# Mixer-v1.net
KiCad netlist of a schematic drawn in EAGLE
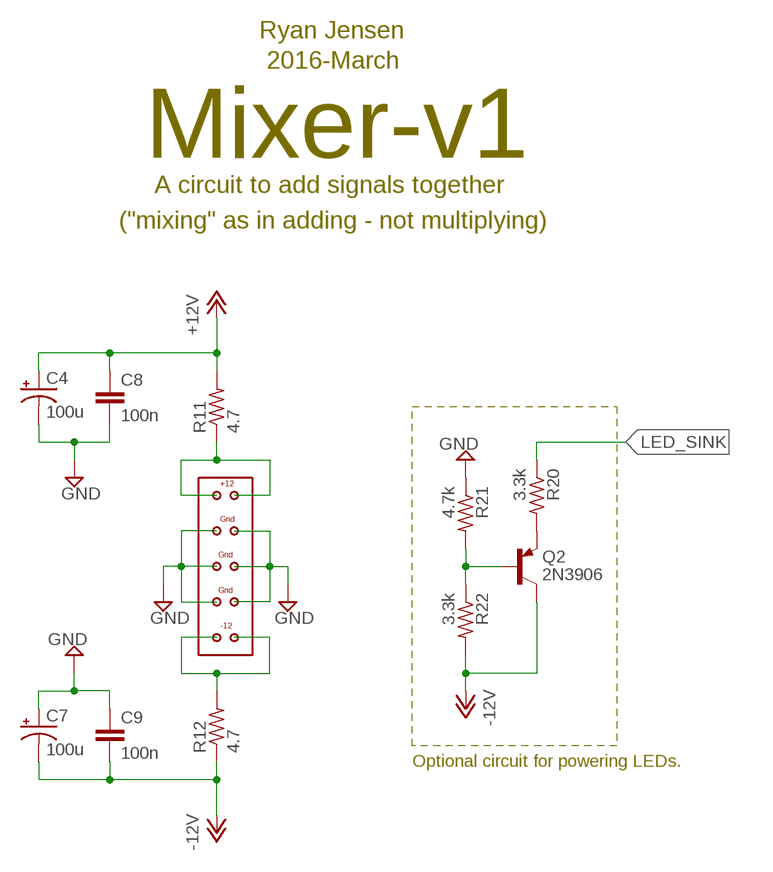
[diagram p0: schematic, sheet 1]
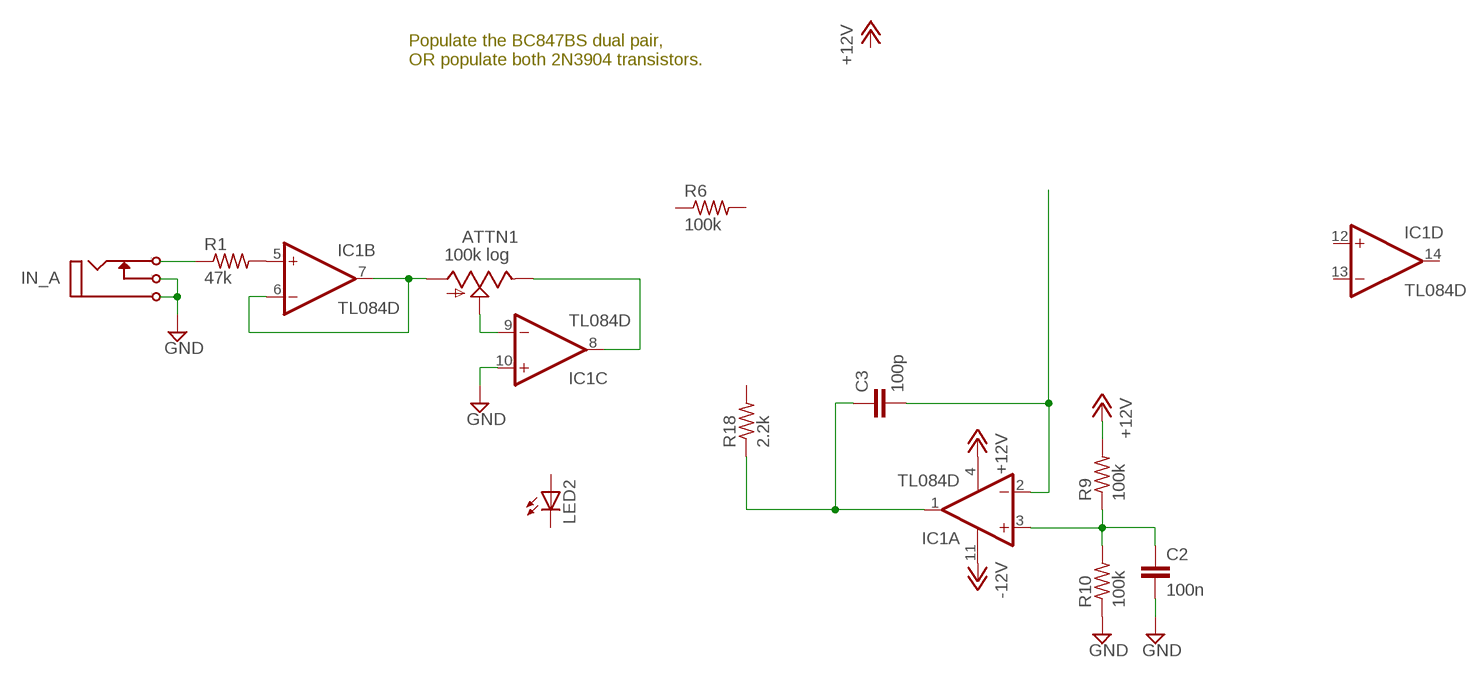
[diagram p1: schematic, sheet 2]

(export (version "E")
  (design (tool "Eeschema 10.0.6"))
  (components
    (comp (ref "ATTN1")
      (value "100k log")
      (footprint "eagle-import:B64Y")
      (libsource (lib "eagle-import") (part "TRIM_US-B64Y"))
    )
    (comp (ref "C2")
      (value "100n")
      (footprint "eagle-import:C0603")
      (libsource (lib "eagle-import") (part "C-EUC0603"))
    )
    (comp (ref "C3")
      (value "100p")
      (footprint "eagle-import:C0603")
      (libsource (lib "eagle-import") (part "C-EUC0603"))
    )
    (comp (ref "IC1")
      (value "TL084D")
      (footprint "eagle-import:SO14")
      (libsource (lib "eagle-import") (part "TL084D"))
    )
    (comp (ref "IN_A")
      (value "CV")
      (footprint "eagle-import:MONO_JACK")
      (libsource (lib "eagle-import") (part "MONO_JACK"))
    )
    (comp (ref "LED2")
      (value "LED_ELD260")
      (footprint "eagle-import:LED_LD260")
      (libsource (lib "eagle-import") (part "LED_ELD260"))
    )
    (comp (ref "R1")
      (value "47k")
      (footprint "eagle-import:R0603")
      (libsource (lib "eagle-import") (part "R-US_R0603"))
    )
    (comp (ref "R6")
      (value "100k")
      (footprint "eagle-import:R0603")
      (libsource (lib "eagle-import") (part "R-US_R0603"))
    )
    (comp (ref "R9")
      (value "100k")
      (footprint "eagle-import:R0603")
      (libsource (lib "eagle-import") (part "R-US_R0603"))
    )
    (comp (ref "R10")
      (value "100k")
      (footprint "eagle-import:R0603")
      (libsource (lib "eagle-import") (part "R-US_R0603"))
    )
    (comp (ref "R18")
      (value "2.2k")
      (footprint "eagle-import:R0603")
      (libsource (lib "eagle-import") (part "R-US_R0603"))
    )
    (comp (ref "C4")
      (value "100u")
      (footprint "eagle-import:E2,5-7")
      (libsource (lib "eagle-import") (part "CPOL-USE2.5-7"))
    )
    (comp (ref "C7")
      (value "100u")
      (footprint "eagle-import:E2,5-7")
      (libsource (lib "eagle-import") (part "CPOL-USE2.5-7"))
    )
    (comp (ref "C8")
      (value "100n")
      (footprint "eagle-import:C0603")
      (libsource (lib "eagle-import") (part "C-EUC0603"))
    )
    (comp (ref "C9")
      (value "100n")
      (footprint "eagle-import:C0603")
      (libsource (lib "eagle-import") (part "C-EUC0603"))
    )
    (comp (ref "Q2")
      (value "2N3906")
      (footprint "eagle-import:TO92")
      (libsource (lib "eagle-import") (part "2N3906"))
    )
    (comp (ref "R11")
      (value "4.7")
      (footprint "eagle-import:R0603")
      (libsource (lib "eagle-import") (part "R-US_R0603"))
    )
    (comp (ref "R12")
      (value "4.7")
      (footprint "eagle-import:R0603")
      (libsource (lib "eagle-import") (part "R-US_R0603"))
    )
    (comp (ref "R20")
      (value "3.3k")
      (footprint "eagle-import:R0603")
      (libsource (lib "eagle-import") (part "R-US_R0603"))
    )
    (comp (ref "R21")
      (value "4.7k")
      (footprint "eagle-import:R0603")
      (libsource (lib "eagle-import") (part "R-US_R0603"))
    )
    (comp (ref "R22")
      (value "3.3k")
      (footprint "eagle-import:R0603")
      (libsource (lib "eagle-import") (part "R-US_R0603"))
    )
    (comp (ref "U$3")
      (value "EURORACK-POWER")
      (footprint "eagle-import:EURORACK-POWER")
      (libsource (lib "eagle-import") (part "EURORACK-POWER"))
    )
  )
  (nets
    (net (code "1") (name "+12V") (class "Default")
      (node (ref "C4") (pin "+") (pinfunction "+_+") (pintype "passive"))
      (node (ref "C8") (pin "1") (pinfunction "1_1") (pintype "passive"))
      (node (ref "IC1") (pin "4") (pinfunction "V+_4") (pintype "power_in"))
      (node (ref "R11") (pin "2") (pinfunction "2_2") (pintype "passive"))
      (node (ref "R9") (pin "2") (pinfunction "2_2") (pintype "passive"))
    )
    (net (code "2") (name "-12V") (class "Default")
      (node (ref "C7") (pin "-") (pinfunction "-_-") (pintype "passive"))
      (node (ref "C9") (pin "2") (pinfunction "2_2") (pintype "passive"))
      (node (ref "IC1") (pin "11") (pinfunction "V-_11") (pintype "power_in"))
      (node (ref "Q2") (pin "1") (pinfunction "C_1") (pintype "passive"))
      (node (ref "R12") (pin "1") (pinfunction "1_1") (pintype "passive"))
      (node (ref "R22") (pin "2") (pinfunction "2_2") (pintype "passive"))
    )
    (net (code "3") (name "GND") (class "Default")
      (node (ref "C2") (pin "2") (pinfunction "2_2") (pintype "passive"))
      (node (ref "C4") (pin "-") (pinfunction "-_-") (pintype "passive"))
      (node (ref "C7") (pin "+") (pinfunction "+_+") (pintype "passive"))
      (node (ref "C8") (pin "2") (pinfunction "2_2") (pintype "passive"))
      (node (ref "C9") (pin "1") (pinfunction "1_1") (pintype "passive"))
      (node (ref "IC1") (pin "10") (pinfunction "+IN_10") (pintype "input"))
      (node (ref "IN_A") (pin "P$1") (pinfunction "P$1_P$1") (pintype "bidirectional"))
      (node (ref "IN_A") (pin "P$3") (pinfunction "P3_P$3") (pintype "bidirectional"))
      (node (ref "R10") (pin "1") (pinfunction "1_1") (pintype "passive"))
      (node (ref "R21") (pin "1") (pinfunction "1_1") (pintype "passive"))
      (node (ref "U$3") (pin "P$3") (pinfunction "P$3_P$3") (pintype "bidirectional"))
      (node (ref "U$3") (pin "P$4") (pinfunction "P$4_P$4") (pintype "bidirectional"))
      (node (ref "U$3") (pin "P$5") (pinfunction "P$5_P$5") (pintype "bidirectional"))
      (node (ref "U$3") (pin "P$6") (pinfunction "P$6_P$6") (pintype "bidirectional"))
      (node (ref "U$3") (pin "P$7") (pinfunction "P$7_P$7") (pintype "bidirectional"))
      (node (ref "U$3") (pin "P$8") (pinfunction "P$8_P$8") (pintype "bidirectional"))
    )
    (net (code "4") (name "LED_SINK") (class "Default")
      (node (ref "R20") (pin "1") (pinfunction "1_1") (pintype "passive"))
    )
    (net (code "5") (name "Net-(IC1A-+IN)") (class "Default")
      (node (ref "C2") (pin "1") (pinfunction "1_1") (pintype "passive"))
      (node (ref "IC1") (pin "3") (pinfunction "+IN_3") (pintype "input"))
      (node (ref "R10") (pin "2") (pinfunction "2_2") (pintype "passive"))
      (node (ref "R9") (pin "1") (pinfunction "1_1") (pintype "passive"))
    )
    (net (code "6") (name "Net-(IC1A--IN)") (class "Default")
      (node (ref "C3") (pin "2") (pinfunction "2_2") (pintype "passive"))
      (node (ref "IC1") (pin "2") (pinfunction "-IN_2") (pintype "input"))
    )
    (net (code "7") (name "Net-(IC1A-OUT)") (class "Default")
      (node (ref "C3") (pin "1") (pinfunction "1_1") (pintype "passive"))
      (node (ref "IC1") (pin "1") (pinfunction "OUT_1") (pintype "output"))
      (node (ref "R18") (pin "1") (pinfunction "1_1") (pintype "passive"))
    )
    (net (code "8") (name "Net-(IC1B-+IN)") (class "Default")
      (node (ref "IC1") (pin "5") (pinfunction "+IN_5") (pintype "input"))
      (node (ref "R1") (pin "2") (pinfunction "2_2") (pintype "passive"))
    )
    (net (code "9") (name "Net-(IC1B--IN)") (class "Default")
      (node (ref "ATTN1") (pin "A") (pinfunction "A_A") (pintype "passive"))
      (node (ref "IC1") (pin "6") (pinfunction "-IN_6") (pintype "input"))
      (node (ref "IC1") (pin "7") (pinfunction "OUT_7") (pintype "output"))
    )
    (net (code "10") (name "Net-(IC1C--IN)") (class "Default")
      (node (ref "ATTN1") (pin "S") (pinfunction "S_S") (pintype "passive"))
      (node (ref "IC1") (pin "9") (pinfunction "-IN_9") (pintype "input"))
    )
    (net (code "11") (name "Net-(IC1C-OUT)") (class "Default")
      (node (ref "ATTN1") (pin "E") (pinfunction "E_E") (pintype "passive"))
      (node (ref "IC1") (pin "8") (pinfunction "OUT_8") (pintype "output"))
    )
    (net (code "12") (name "Net-(IN_A-P2)") (class "Default")
      (node (ref "IN_A") (pin "P$2") (pinfunction "P2_P$2") (pintype "bidirectional"))
      (node (ref "R1") (pin "1") (pinfunction "1_1") (pintype "passive"))
    )
    (net (code "13") (name "Net-(Q2-B)") (class "Default")
      (node (ref "Q2") (pin "2") (pinfunction "B_2") (pintype "passive"))
      (node (ref "R21") (pin "2") (pinfunction "2_2") (pintype "passive"))
      (node (ref "R22") (pin "1") (pinfunction "1_1") (pintype "passive"))
    )
    (net (code "14") (name "Net-(Q2-E)") (class "Default")
      (node (ref "Q2") (pin "3") (pinfunction "E_3") (pintype "passive"))
      (node (ref "R20") (pin "2") (pinfunction "2_2") (pintype "passive"))
    )
    (net (code "15") (name "Net-(R11-Pad1)") (class "Default")
      (node (ref "R11") (pin "1") (pinfunction "1_1") (pintype "passive"))
      (node (ref "U$3") (pin "P$1") (pinfunction "P$1_P$1") (pintype "bidirectional"))
      (node (ref "U$3") (pin "P$2") (pinfunction "P$2_P$2") (pintype "bidirectional"))
    )
    (net (code "16") (name "Net-(R12-Pad2)") (class "Default")
      (node (ref "R12") (pin "2") (pinfunction "2_2") (pintype "passive"))
      (node (ref "U$3") (pin "P$10") (pinfunction "P$10_P$10") (pintype "bidirectional"))
      (node (ref "U$3") (pin "P$9") (pinfunction "P$9_P$9") (pintype "bidirectional"))
    )
    (net (code "17") (name "unconnected-(IC1D-+IN-Pad12)") (class "Default")
      (node (ref "IC1") (pin "12") (pinfunction "+IN_12") (pintype "input"))
    )
    (net (code "18") (name "unconnected-(IC1D--IN-Pad13)") (class "Default")
      (node (ref "IC1") (pin "13") (pinfunction "-IN_13") (pintype "input"))
    )
    (net (code "19") (name "unconnected-(IC1D-OUT-Pad14)") (class "Default")
      (node (ref "IC1") (pin "14") (pinfunction "OUT_14") (pintype "output"))
    )
    (net (code "20") (name "unconnected-(LED2-C-PadK)") (class "Default")
      (node (ref "LED2") (pin "K") (pinfunction "C_K") (pintype "passive"))
    )
    (net (code "21") (name "unconnected-(LED2-PadA)") (class "Default")
      (node (ref "LED2") (pin "A") (pinfunction "A_A") (pintype "passive"))
    )
    (net (code "22") (name "unconnected-(R6-Pad1)") (class "Default")
      (node (ref "R6") (pin "1") (pinfunction "1_1") (pintype "passive"))
    )
    (net (code "23") (name "unconnected-(R6-Pad2)") (class "Default")
      (node (ref "R6") (pin "2") (pinfunction "2_2") (pintype "passive"))
    )
    (net (code "24") (name "unconnected-(R18-Pad2)") (class "Default")
      (node (ref "R18") (pin "2") (pinfunction "2_2") (pintype "passive"))
    )
  )
)
